# RHD2132_lvds_headstage_50mil_v2.net
KiCad netlist of a schematic drawn in EAGLE
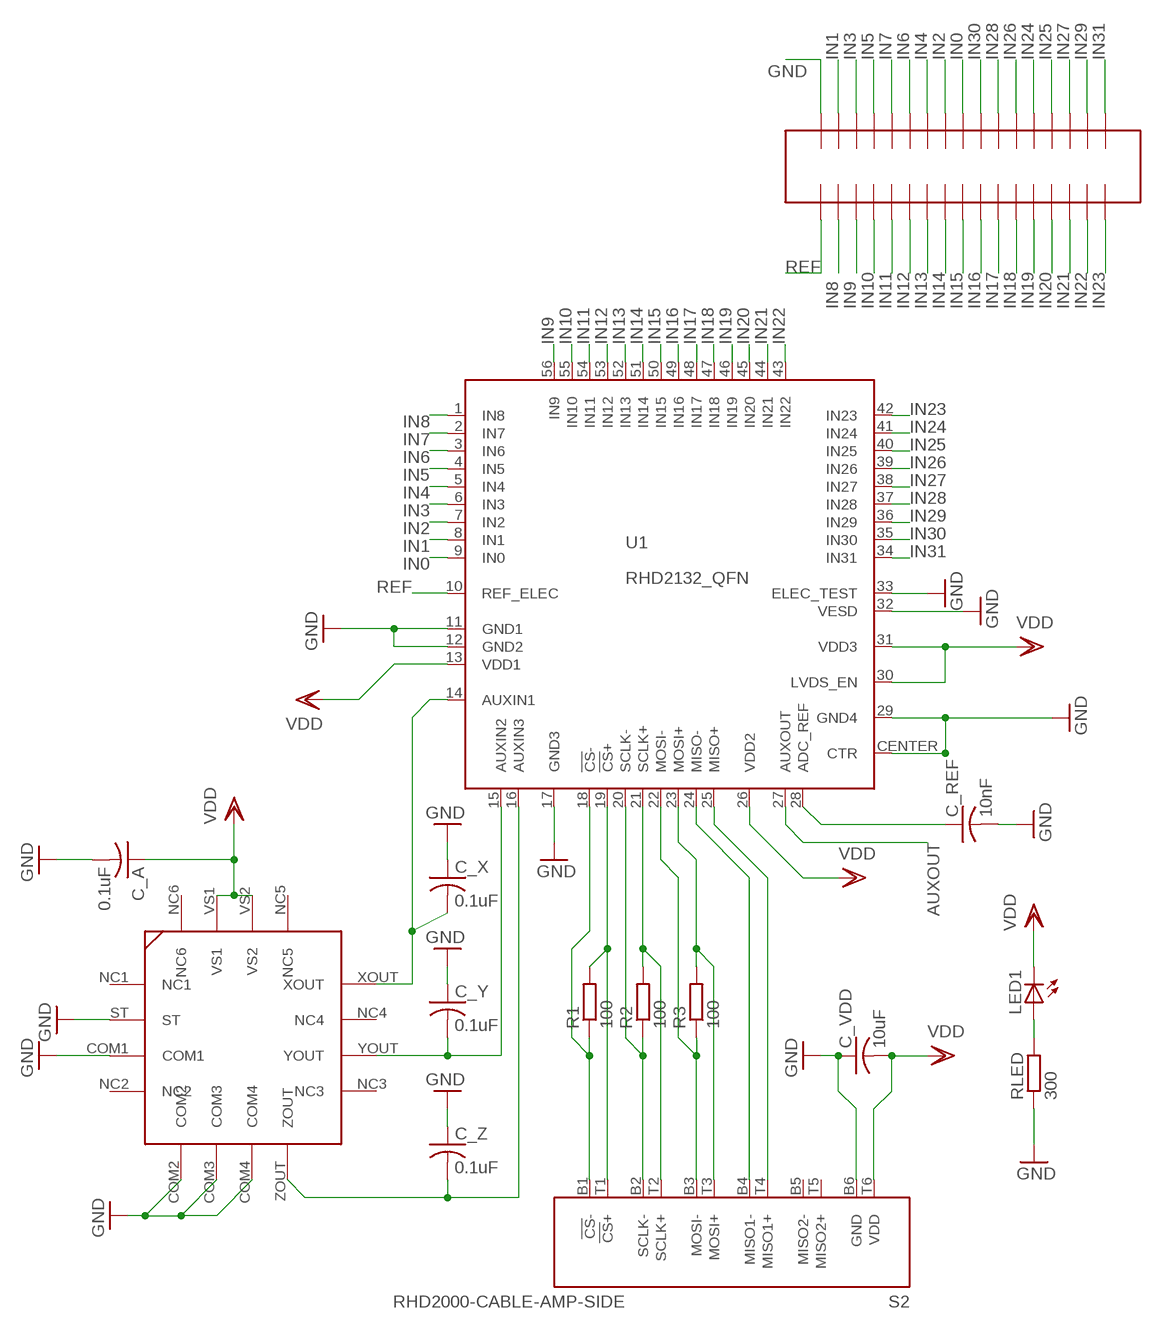
[diagram p0: schematic, sheet 1]

(export (version "E")
  (design (tool "Eeschema 10.0.6"))
  (components
    (comp (ref "C_A")
      (value "0.1uF")
      (footprint "eagle-import:C0402K")
      (libsource (lib "eagle-import") (part "resistor_C-USC0402K"))
    )
    (comp (ref "C_REF")
      (value "10nF")
      (footprint "eagle-import:C0402K")
      (libsource (lib "eagle-import") (part "resistor_C-USC0402K"))
    )
    (comp (ref "C_VDD")
      (value "10uF")
      (footprint "eagle-import:C0805")
      (libsource (lib "eagle-import") (part "C-USC0805"))
    )
    (comp (ref "C_X")
      (value "0.1uF")
      (footprint "eagle-import:C0402K")
      (libsource (lib "eagle-import") (part "resistor_C-USC0402K"))
    )
    (comp (ref "C_Y")
      (value "0.1uF")
      (footprint "eagle-import:C0402K")
      (libsource (lib "eagle-import") (part "resistor_C-USC0402K"))
    )
    (comp (ref "C_Z")
      (value "0.1uF")
      (footprint "eagle-import:C0402K")
      (libsource (lib "eagle-import") (part "resistor_C-USC0402K"))
    )
    (comp (ref "LED1")
      (value "LEDCHIPLED_0805")
      (footprint "eagle-import:CHIPLED_0805")
      (libsource (lib "eagle-import") (part "LEDCHIPLED_0805"))
    )
    (comp (ref "R1")
      (value "100")
      (footprint "eagle-import:R0402")
      (libsource (lib "eagle-import") (part "R-EU_R0402"))
    )
    (comp (ref "R2")
      (value "100")
      (footprint "eagle-import:R0402")
      (libsource (lib "eagle-import") (part "R-EU_R0402"))
    )
    (comp (ref "R3")
      (value "100")
      (footprint "eagle-import:R0402")
      (libsource (lib "eagle-import") (part "R-EU_R0402"))
    )
    (comp (ref "RLED")
      (value "300")
      (footprint "eagle-import:R0402")
      (libsource (lib "eagle-import") (part "R-EU_R0402"))
    )
    (comp (ref "S2")
      (value "RHD2000-CABLE-AMP-SIDE")
      (footprint "eagle-import:OMNETICS_PZN-12-AA")
      (libsource (lib "eagle-import") (part "RHD2000-CABLE-AMP-SIDE"))
    )
    (comp (ref "U$1")
      (value "ADXL335")
      (footprint "eagle-import:ADXL335")
      (libsource (lib "eagle-import") (part "ADXL335"))
    )
    (comp (ref "U$2")
      (value "FTSH-117BOARD-END")
      (footprint "eagle-import:FTSH-117-END")
      (libsource (lib "eagle-import") (part "FTSH-117BOARD-END"))
    )
    (comp (ref "U1")
      (value "RHD2132_QFN")
      (footprint "eagle-import:QFN56_8_X_8_LARGE")
      (libsource (lib "eagle-import") (part "RHD2132_QFN"))
    )
  )
  (nets
    (net (code "1") (name "/AUXOUT") (class "Default")
      (node (ref "U1") (pin "27") (pinfunction "AUXOUT_27") (pintype "tri_state"))
    )
    (net (code "2") (name "/IN0") (class "Default")
      (node (ref "U$2") (pin "P$26") (pinfunction "P$26_P$26") (pintype "bidirectional"))
      (node (ref "U1") (pin "9") (pinfunction "IN0_9") (pintype "input"))
    )
    (net (code "3") (name "/IN1") (class "Default")
      (node (ref "U$2") (pin "P$33") (pinfunction "P$33_P$33") (pintype "bidirectional"))
      (node (ref "U1") (pin "8") (pinfunction "IN1_8") (pintype "input"))
    )
    (net (code "4") (name "/IN2") (class "Default")
      (node (ref "U$2") (pin "P$27") (pinfunction "P$27_P$27") (pintype "bidirectional"))
      (node (ref "U1") (pin "7") (pinfunction "IN2_7") (pintype "input"))
    )
    (net (code "5") (name "/IN3") (class "Default")
      (node (ref "U$2") (pin "P$32") (pinfunction "P$32_P$32") (pintype "bidirectional"))
      (node (ref "U1") (pin "6") (pinfunction "IN3_6") (pintype "input"))
    )
    (net (code "6") (name "/IN4") (class "Default")
      (node (ref "U$2") (pin "P$28") (pinfunction "P$28_P$28") (pintype "bidirectional"))
      (node (ref "U1") (pin "5") (pinfunction "IN4_5") (pintype "input"))
    )
    (net (code "7") (name "/IN5") (class "Default")
      (node (ref "U$2") (pin "P$31") (pinfunction "P$31_P$31") (pintype "bidirectional"))
      (node (ref "U1") (pin "4") (pinfunction "IN5_4") (pintype "input"))
    )
    (net (code "8") (name "/IN6") (class "Default")
      (node (ref "U$2") (pin "P$29") (pinfunction "P$29_P$29") (pintype "bidirectional"))
      (node (ref "U1") (pin "3") (pinfunction "IN6_3") (pintype "input"))
    )
    (net (code "9") (name "/IN7") (class "Default")
      (node (ref "U$2") (pin "P$30") (pinfunction "P$30_P$30") (pintype "bidirectional"))
      (node (ref "U1") (pin "2") (pinfunction "IN7_2") (pintype "input"))
    )
    (net (code "10") (name "/IN8") (class "Default")
      (node (ref "U$2") (pin "P$2") (pinfunction "P$2_P$2") (pintype "bidirectional"))
      (node (ref "U1") (pin "1") (pinfunction "IN8_1") (pintype "input"))
    )
    (net (code "11") (name "/IN9") (class "Default")
      (node (ref "U$2") (pin "P$3") (pinfunction "P$3_P$3") (pintype "bidirectional"))
      (node (ref "U1") (pin "56") (pinfunction "IN9_56") (pintype "input"))
    )
    (net (code "12") (name "/IN10") (class "Default")
      (node (ref "U$2") (pin "P$4") (pinfunction "P$4_P$4") (pintype "bidirectional"))
      (node (ref "U1") (pin "55") (pinfunction "IN10_55") (pintype "input"))
    )
    (net (code "13") (name "/IN11") (class "Default")
      (node (ref "U$2") (pin "P$5") (pinfunction "P$5_P$5") (pintype "bidirectional"))
      (node (ref "U1") (pin "54") (pinfunction "IN11_54") (pintype "input"))
    )
    (net (code "14") (name "/IN12") (class "Default")
      (node (ref "U$2") (pin "P$6") (pinfunction "P$6_P$6") (pintype "bidirectional"))
      (node (ref "U1") (pin "53") (pinfunction "IN12_53") (pintype "input"))
    )
    (net (code "15") (name "/IN13") (class "Default")
      (node (ref "U$2") (pin "P$7") (pinfunction "P$7_P$7") (pintype "bidirectional"))
      (node (ref "U1") (pin "52") (pinfunction "IN13_52") (pintype "input"))
    )
    (net (code "16") (name "/IN14") (class "Default")
      (node (ref "U$2") (pin "P$8") (pinfunction "P$8_P$8") (pintype "bidirectional"))
      (node (ref "U1") (pin "51") (pinfunction "IN14_51") (pintype "input"))
    )
    (net (code "17") (name "/IN15") (class "Default")
      (node (ref "U$2") (pin "P$9") (pinfunction "P$9_P$9") (pintype "bidirectional"))
      (node (ref "U1") (pin "50") (pinfunction "IN15_50") (pintype "input"))
    )
    (net (code "18") (name "/IN16") (class "Default")
      (node (ref "U$2") (pin "P$10") (pinfunction "P$10_P$10") (pintype "bidirectional"))
      (node (ref "U1") (pin "49") (pinfunction "IN16_49") (pintype "input"))
    )
    (net (code "19") (name "/IN17") (class "Default")
      (node (ref "U$2") (pin "P$11") (pinfunction "P$11_P$11") (pintype "bidirectional"))
      (node (ref "U1") (pin "48") (pinfunction "IN17_48") (pintype "input"))
    )
    (net (code "20") (name "/IN18") (class "Default")
      (node (ref "U$2") (pin "P$12") (pinfunction "P$12_P$12") (pintype "bidirectional"))
      (node (ref "U1") (pin "47") (pinfunction "IN18_47") (pintype "input"))
    )
    (net (code "21") (name "/IN19") (class "Default")
      (node (ref "U$2") (pin "P$13") (pinfunction "P$13_P$13") (pintype "bidirectional"))
      (node (ref "U1") (pin "46") (pinfunction "IN19_46") (pintype "input"))
    )
    (net (code "22") (name "/IN20") (class "Default")
      (node (ref "U$2") (pin "P$14") (pinfunction "P$14_P$14") (pintype "bidirectional"))
      (node (ref "U1") (pin "45") (pinfunction "IN20_45") (pintype "input"))
    )
    (net (code "23") (name "/IN21") (class "Default")
      (node (ref "U$2") (pin "P$15") (pinfunction "P$15_P$15") (pintype "bidirectional"))
      (node (ref "U1") (pin "44") (pinfunction "IN21_44") (pintype "input"))
    )
    (net (code "24") (name "/IN22") (class "Default")
      (node (ref "U$2") (pin "P$16") (pinfunction "P$16_P$16") (pintype "bidirectional"))
      (node (ref "U1") (pin "43") (pinfunction "IN22_43") (pintype "input"))
    )
    (net (code "25") (name "/IN23") (class "Default")
      (node (ref "U$2") (pin "P$17") (pinfunction "P$17_P$17") (pintype "bidirectional"))
      (node (ref "U1") (pin "42") (pinfunction "IN23_42") (pintype "input"))
    )
    (net (code "26") (name "/IN24") (class "Default")
      (node (ref "U$2") (pin "P$22") (pinfunction "P$22_P$22") (pintype "bidirectional"))
      (node (ref "U1") (pin "41") (pinfunction "IN24_41") (pintype "input"))
    )
    (net (code "27") (name "/IN25") (class "Default")
      (node (ref "U$2") (pin "P$21") (pinfunction "P$21_P$21") (pintype "bidirectional"))
      (node (ref "U1") (pin "40") (pinfunction "IN25_40") (pintype "input"))
    )
    (net (code "28") (name "/IN26") (class "Default")
      (node (ref "U$2") (pin "P$23") (pinfunction "P$23_P$23") (pintype "bidirectional"))
      (node (ref "U1") (pin "39") (pinfunction "IN26_39") (pintype "input"))
    )
    (net (code "29") (name "/IN27") (class "Default")
      (node (ref "U$2") (pin "P$20") (pinfunction "P$20_P$20") (pintype "bidirectional"))
      (node (ref "U1") (pin "38") (pinfunction "IN27_38") (pintype "input"))
    )
    (net (code "30") (name "/IN28") (class "Default")
      (node (ref "U$2") (pin "P$24") (pinfunction "P$24_P$24") (pintype "bidirectional"))
      (node (ref "U1") (pin "37") (pinfunction "IN28_37") (pintype "input"))
    )
    (net (code "31") (name "/IN29") (class "Default")
      (node (ref "U$2") (pin "P$19") (pinfunction "P$19_P$19") (pintype "bidirectional"))
      (node (ref "U1") (pin "36") (pinfunction "IN29_36") (pintype "input"))
    )
    (net (code "32") (name "/IN30") (class "Default")
      (node (ref "U$2") (pin "P$25") (pinfunction "P$25_P$25") (pintype "bidirectional"))
      (node (ref "U1") (pin "35") (pinfunction "IN30_35") (pintype "input"))
    )
    (net (code "33") (name "/IN31") (class "Default")
      (node (ref "U$2") (pin "P$18") (pinfunction "P$18_P$18") (pintype "bidirectional"))
      (node (ref "U1") (pin "34") (pinfunction "IN31_34") (pintype "input"))
    )
    (net (code "34") (name "/REF") (class "Default")
      (node (ref "U$2") (pin "P$1") (pinfunction "P$1_P$1") (pintype "bidirectional"))
      (node (ref "U1") (pin "10") (pinfunction "REF_ELEC_10") (pintype "input"))
    )
    (net (code "35") (name "GND") (class "Default")
      (node (ref "C_A") (pin "2") (pinfunction "2_2") (pintype "passive"))
      (node (ref "C_REF") (pin "2") (pinfunction "2_2") (pintype "passive"))
      (node (ref "C_VDD") (pin "1") (pinfunction "1_1") (pintype "passive"))
      (node (ref "C_X") (pin "1") (pinfunction "1_1") (pintype "passive"))
      (node (ref "C_Y") (pin "1") (pinfunction "1_1") (pintype "passive"))
      (node (ref "C_Z") (pin "1") (pinfunction "1_1") (pintype "passive"))
      (node (ref "RLED") (pin "1") (pinfunction "1_1") (pintype "passive"))
      (node (ref "S2") (pin "B6") (pinfunction "GND_B6") (pintype "power_in"))
      (node (ref "U$1") (pin "COM1") (pinfunction "COM1_COM1") (pintype "bidirectional"))
      (node (ref "U$1") (pin "COM2") (pinfunction "COM2_COM2") (pintype "bidirectional"))
      (node (ref "U$1") (pin "COM3") (pinfunction "COM3_COM3") (pintype "bidirectional"))
      (node (ref "U$1") (pin "COM4") (pinfunction "COM4_COM4") (pintype "bidirectional"))
      (node (ref "U$1") (pin "ST") (pinfunction "ST_ST") (pintype "bidirectional"))
      (node (ref "U$2") (pin "P$34") (pinfunction "P$34_P$34") (pintype "bidirectional"))
      (node (ref "U1") (pin "11") (pinfunction "GND1_11") (pintype "power_in"))
      (node (ref "U1") (pin "12") (pinfunction "GND2_12") (pintype "power_in"))
      (node (ref "U1") (pin "17") (pinfunction "GND3_17") (pintype "power_in"))
      (node (ref "U1") (pin "29") (pinfunction "GND4_29") (pintype "power_in"))
      (node (ref "U1") (pin "32") (pinfunction "VESD_32") (pintype "power_in"))
      (node (ref "U1") (pin "33") (pinfunction "ELEC_TEST_33") (pintype "input"))
      (node (ref "U1") (pin "CENTER") (pinfunction "CTR_CENTER") (pintype "power_in"))
    )
    (net (code "36") (name "Net-(LED1-PadA)") (class "Default")
      (node (ref "LED1") (pin "A") (pinfunction "A_A") (pintype "passive"))
      (node (ref "RLED") (pin "2") (pinfunction "2_2") (pintype "passive"))
    )
    (net (code "37") (name "Net-(S2-MISO1+)") (class "Default")
      (node (ref "S2") (pin "T4") (pinfunction "MISO1+_T4") (pintype "bidirectional"))
      (node (ref "U1") (pin "25") (pinfunction "MISO+_25") (pintype "output"))
    )
    (net (code "38") (name "Net-(S2-MISO1-)") (class "Default")
      (node (ref "S2") (pin "B4") (pinfunction "MISO1-_B4") (pintype "bidirectional"))
      (node (ref "U1") (pin "24") (pinfunction "MISO-_24") (pintype "output"))
    )
    (net (code "39") (name "Net-(S2-MOSI+)") (class "Default")
      (node (ref "R3") (pin "2") (pinfunction "2_2") (pintype "passive"))
      (node (ref "S2") (pin "T3") (pinfunction "MOSI+_T3") (pintype "bidirectional"))
      (node (ref "U1") (pin "23") (pinfunction "MOSI+_23") (pintype "input"))
    )
    (net (code "40") (name "Net-(S2-MOSI-)") (class "Default")
      (node (ref "R3") (pin "1") (pinfunction "1_1") (pintype "passive"))
      (node (ref "S2") (pin "B3") (pinfunction "MOSI-_B3") (pintype "bidirectional"))
      (node (ref "U1") (pin "22") (pinfunction "MOSI-_22") (pintype "input"))
    )
    (net (code "41") (name "Net-(S2-SCLK+)") (class "Default")
      (node (ref "R2") (pin "2") (pinfunction "2_2") (pintype "passive"))
      (node (ref "S2") (pin "T2") (pinfunction "SCLK+_T2") (pintype "bidirectional"))
      (node (ref "U1") (pin "21") (pinfunction "SCLK+_21") (pintype "input"))
    )
    (net (code "42") (name "Net-(S2-SCLK-)") (class "Default")
      (node (ref "R2") (pin "1") (pinfunction "1_1") (pintype "passive"))
      (node (ref "S2") (pin "B2") (pinfunction "SCLK-_B2") (pintype "bidirectional"))
      (node (ref "U1") (pin "20") (pinfunction "SCLK-_20") (pintype "input"))
    )
    (net (code "43") (name "Net-(S2-~{CS}+)") (class "Default")
      (node (ref "R1") (pin "2") (pinfunction "2_2") (pintype "passive"))
      (node (ref "S2") (pin "T1") (pinfunction "~{CS}+_T1") (pintype "bidirectional"))
      (node (ref "U1") (pin "19") (pinfunction "~{CS}+_19") (pintype "input"))
    )
    (net (code "44") (name "Net-(S2-~{CS}-)") (class "Default")
      (node (ref "R1") (pin "1") (pinfunction "1_1") (pintype "passive"))
      (node (ref "S2") (pin "B1") (pinfunction "~{CS}-_B1") (pintype "bidirectional"))
      (node (ref "U1") (pin "18") (pinfunction "~{CS}-_18") (pintype "input"))
    )
    (net (code "45") (name "Net-(U1-ADC_REF)") (class "Default")
      (node (ref "C_REF") (pin "1") (pinfunction "1_1") (pintype "passive"))
      (node (ref "U1") (pin "28") (pinfunction "ADC_REF_28") (pintype "passive"))
    )
    (net (code "46") (name "Net-(U1-AUXIN1)") (class "Default")
      (node (ref "C_X") (pin "2") (pinfunction "2_2") (pintype "passive"))
      (node (ref "U$1") (pin "XOUT") (pinfunction "XOUT_XOUT") (pintype "bidirectional"))
      (node (ref "U1") (pin "14") (pinfunction "AUXIN1_14") (pintype "input"))
    )
    (net (code "47") (name "Net-(U1-AUXIN2)") (class "Default")
      (node (ref "C_Y") (pin "2") (pinfunction "2_2") (pintype "passive"))
      (node (ref "U$1") (pin "YOUT") (pinfunction "YOUT_YOUT") (pintype "bidirectional"))
      (node (ref "U1") (pin "15") (pinfunction "AUXIN2_15") (pintype "input"))
    )
    (net (code "48") (name "Net-(U1-AUXIN3)") (class "Default")
      (node (ref "C_Z") (pin "2") (pinfunction "2_2") (pintype "passive"))
      (node (ref "U$1") (pin "ZOUT") (pinfunction "ZOUT_ZOUT") (pintype "bidirectional"))
      (node (ref "U1") (pin "16") (pinfunction "AUXIN3_16") (pintype "input"))
    )
    (net (code "49") (name "VDD") (class "Default")
      (node (ref "C_A") (pin "1") (pinfunction "1_1") (pintype "passive"))
      (node (ref "C_VDD") (pin "2") (pinfunction "2_2") (pintype "passive"))
      (node (ref "LED1") (pin "C") (pinfunction "C_C") (pintype "passive"))
      (node (ref "S2") (pin "T6") (pinfunction "VDD_T6") (pintype "bidirectional"))
      (node (ref "U$1") (pin "VS1") (pinfunction "VS1_VS1") (pintype "bidirectional"))
      (node (ref "U$1") (pin "VS2") (pinfunction "VS2_VS2") (pintype "bidirectional"))
      (node (ref "U1") (pin "13") (pinfunction "VDD1_13") (pintype "power_in"))
      (node (ref "U1") (pin "26") (pinfunction "VDD2_26") (pintype "power_in"))
      (node (ref "U1") (pin "30") (pinfunction "LVDS_EN_30") (pintype "input"))
      (node (ref "U1") (pin "31") (pinfunction "VDD3_31") (pintype "power_in"))
    )
    (net (code "50") (name "unconnected-(S2-MISO2+-PadT5)") (class "Default")
      (node (ref "S2") (pin "T5") (pinfunction "MISO2+_T5") (pintype "bidirectional"))
    )
    (net (code "51") (name "unconnected-(S2-MISO2--PadB5)") (class "Default")
      (node (ref "S2") (pin "B5") (pinfunction "MISO2-_B5") (pintype "bidirectional"))
    )
    (net (code "52") (name "unconnected-(U$1-PadNC1)") (class "Default")
      (node (ref "U$1") (pin "NC1") (pinfunction "NC1_NC1") (pintype "bidirectional"))
    )
    (net (code "53") (name "unconnected-(U$1-PadNC2)") (class "Default")
      (node (ref "U$1") (pin "NC2") (pinfunction "NC2_NC2") (pintype "bidirectional"))
    )
    (net (code "54") (name "unconnected-(U$1-PadNC3)") (class "Default")
      (node (ref "U$1") (pin "NC3") (pinfunction "NC3_NC3") (pintype "bidirectional"))
    )
    (net (code "55") (name "unconnected-(U$1-PadNC4)") (class "Default")
      (node (ref "U$1") (pin "NC4") (pinfunction "NC4_NC4") (pintype "bidirectional"))
    )
    (net (code "56") (name "unconnected-(U$1-PadNC5)") (class "Default")
      (node (ref "U$1") (pin "NC5") (pinfunction "NC5_NC5") (pintype "bidirectional"))
    )
    (net (code "57") (name "unconnected-(U$1-PadNC6)") (class "Default")
      (node (ref "U$1") (pin "NC6") (pinfunction "NC6_NC6") (pintype "bidirectional"))
    )
  )
)
